# ESP32.net
KiCad netlist of a schematic drawn in Altium Designer
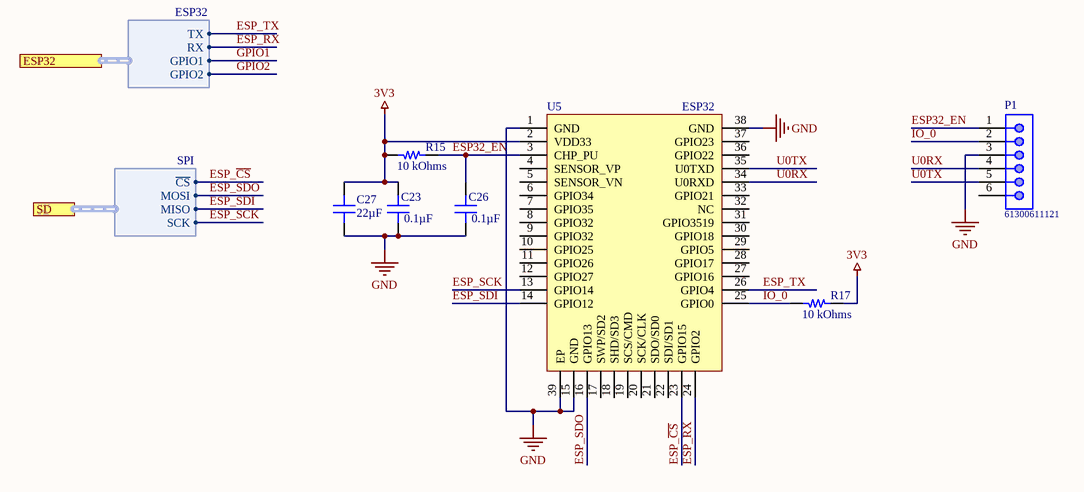
[diagram p0: ESP32.SchDoc]

(export (version "E")
  (design (tool "Eeschema 10.0.6"))
  (components
    (comp (ref "C23")
      (value "0.1µF")
      (footprint "CAP 0603_1608")
      (description "CAP CER 0.1UF 100V 0603 EPOXY")
      (fields
        (field (name "PART NUMBER") "GCG188R92A104KA03D")
        (field (name "MANUFACTURER") "Murata Electronics")
      )
      (libsource (lib "Celestial Altium Library - altium_library") (part "Capacitor"))
    )
    (comp (ref "C26")
      (value "0.1µF")
      (footprint "CAP 0603_1608")
      (description "CAP CER 0.1UF 100V 0603 EPOXY")
      (fields
        (field (name "PART NUMBER") "GCG188R92A104KA03D")
        (field (name "MANUFACTURER") "Murata Electronics")
      )
      (libsource (lib "Celestial Altium Library - altium_library") (part "Capacitor"))
    )
    (comp (ref "C27")
      (value "22µF")
      (footprint "CAP 0805_2012")
      (description "CAP CER 22UF 16V X5R 0805")
      (fields
        (field (name "PART NUMBER") "CL21A226MOQNNNE")
        (field (name "MANUFACTURER") "Samsung Electro-Mechanics")
      )
      (libsource (lib "Celestial Altium Library - altium_library") (part "Capacitor"))
    )
    (comp (ref "P1")
      (value "61300611121")
      (footprint "61300611121")
      (description "WR-PHD Pin Header, THT, pitch 2.54mm, Single Row, Vertical, 6p")
      (fields (field (name "MANUFACTURER") "Wurth Elektronik"))
      (libsource (lib "Altium_WR-PHD") (part "61300611121"))
    )
    (comp (ref "R15")
      (value "10 kOhms")
      (footprint "RES 0603_1608")
      (description "RES 10K OHM 0.1% 1/16W 0603")
      (fields
        (field (name "PART NUMBER") "RNCS0603BKE10K0")
        (field (name "MANUFACTURER") "Stackpole Electronics Inc")
      )
      (libsource (lib "Celestial Altium Library - altium_library") (part "Resistor"))
    )
    (comp (ref "R17")
      (value "10 kOhms")
      (footprint "RES 0603_1608")
      (description "RES 10K OHM 0.1% 1/16W 0603")
      (fields
        (field (name "PART NUMBER") "RNCS0603BKE10K0")
        (field (name "MANUFACTURER") "Stackpole Electronics Inc")
      )
      (libsource (lib "Celestial Altium Library - altium_library") (part "Resistor"))
    )
    (comp (ref "U5")
      (value "ESP32")
      (footprint "Espressif ESP32-WROOM-32")
      (libsource (lib "IC") (part "ESP32"))
    )
  )
  (nets
    (net (code "3") (name "/ESP32_EN") (class "Default")
      (node (ref "C26") (pin "1") (pinfunction "1_1") (pintype "passive"))
      (node (ref "P1") (pin "1") (pinfunction "1_1") (pintype "passive"))
      (node (ref "R15") (pin "1") (pinfunction "1_1") (pintype "passive"))
      (node (ref "U5") (pin "3") (pinfunction "CHP_PU_3") (pintype "passive"))
    )
    (net (code "4") (name "/ESP_RX") (class "Default")
      (node (ref "U5") (pin "24") (pinfunction "GPIO2_24") (pintype "passive"))
    )
    (net (code "5") (name "/ESP_SCK") (class "Default")
      (node (ref "U5") (pin "13") (pinfunction "GPIO14_13") (pintype "passive"))
    )
    (net (code "6") (name "/ESP_SDI") (class "Default")
      (node (ref "U5") (pin "14") (pinfunction "GPIO12_14") (pintype "passive"))
    )
    (net (code "7") (name "/ESP_SDO") (class "Default")
      (node (ref "U5") (pin "16") (pinfunction "GPIO13_16") (pintype "passive"))
    )
    (net (code "8") (name "/ESP_TX") (class "Default")
      (node (ref "U5") (pin "26") (pinfunction "GPIO4_26") (pintype "passive"))
    )
    (net (code "9") (name "/ESP_~{CS}") (class "Default")
      (node (ref "U5") (pin "23") (pinfunction "GPIO15_23") (pintype "passive"))
    )
    (net (code "12") (name "/IO_0") (class "Default")
      (node (ref "P1") (pin "2") (pinfunction "2_2") (pintype "passive"))
      (node (ref "R17") (pin "2") (pinfunction "2_2") (pintype "passive"))
      (node (ref "U5") (pin "25") (pinfunction "GPIO0_25") (pintype "passive"))
    )
    (net (code "13") (name "/U0RX") (class "Default")
      (node (ref "P1") (pin "4") (pinfunction "4_4") (pintype "passive"))
      (node (ref "U5") (pin "34") (pinfunction "U0RXD_34") (pintype "passive"))
    )
    (net (code "14") (name "/U0TX") (class "Default")
      (node (ref "P1") (pin "5") (pinfunction "5_5") (pintype "passive"))
      (node (ref "U5") (pin "35") (pinfunction "U0TXD_35") (pintype "passive"))
    )
    (net (code "17") (name "3V3") (class "Default")
      (node (ref "C23") (pin "1") (pinfunction "1_1") (pintype "passive"))
      (node (ref "C27") (pin "2") (pinfunction "2_2") (pintype "passive"))
      (node (ref "R15") (pin "2") (pinfunction "2_2") (pintype "passive"))
      (node (ref "R17") (pin "1") (pinfunction "1_1") (pintype "passive"))
      (node (ref "U5") (pin "2") (pinfunction "VDD33_2") (pintype "passive"))
    )
    (net (code "18") (name "GND") (class "Default")
      (node (ref "C23") (pin "2") (pinfunction "2_2") (pintype "passive"))
      (node (ref "C26") (pin "2") (pinfunction "2_2") (pintype "passive"))
      (node (ref "C27") (pin "1") (pinfunction "1_1") (pintype "passive"))
      (node (ref "P1") (pin "3") (pinfunction "3_3") (pintype "passive"))
      (node (ref "U5") (pin "1") (pinfunction "GND_1") (pintype "passive"))
      (node (ref "U5") (pin "15") (pinfunction "GND_15") (pintype "passive"))
      (node (ref "U5") (pin "38") (pinfunction "GND_38") (pintype "passive"))
      (node (ref "U5") (pin "39") (pinfunction "EP_39") (pintype "passive"))
    )
    (net (code "19") (name "unconnected-(P1-Pad6)") (class "Default")
      (node (ref "P1") (pin "6") (pinfunction "6_6") (pintype "passive"))
    )
    (net (code "20") (name "unconnected-(U5-GPIO5-Pad29)") (class "Default")
      (node (ref "U5") (pin "29") (pinfunction "GPIO5_29") (pintype "passive"))
    )
    (net (code "21") (name "unconnected-(U5-GPIO16-Pad27)") (class "Default")
      (node (ref "U5") (pin "27") (pinfunction "GPIO16_27") (pintype "passive"))
    )
    (net (code "22") (name "unconnected-(U5-GPIO17-Pad28)") (class "Default")
      (node (ref "U5") (pin "28") (pinfunction "GPIO17_28") (pintype "passive"))
    )
    (net (code "23") (name "unconnected-(U5-GPIO18-Pad30)") (class "Default")
      (node (ref "U5") (pin "30") (pinfunction "GPIO18_30") (pintype "passive"))
    )
    (net (code "24") (name "unconnected-(U5-GPIO21-Pad33)") (class "Default")
      (node (ref "U5") (pin "33") (pinfunction "GPIO21_33") (pintype "passive"))
    )
    (net (code "25") (name "unconnected-(U5-GPIO22-Pad36)") (class "Default")
      (node (ref "U5") (pin "36") (pinfunction "GPIO22_36") (pintype "passive"))
    )
    (net (code "26") (name "unconnected-(U5-GPIO23-Pad37)") (class "Default")
      (node (ref "U5") (pin "37") (pinfunction "GPIO23_37") (pintype "passive"))
    )
    (net (code "27") (name "unconnected-(U5-GPIO25-Pad10)") (class "Default")
      (node (ref "U5") (pin "10") (pinfunction "GPIO25_10") (pintype "passive"))
    )
    (net (code "28") (name "unconnected-(U5-GPIO26-Pad11)") (class "Default")
      (node (ref "U5") (pin "11") (pinfunction "GPIO26_11") (pintype "passive"))
    )
    (net (code "29") (name "unconnected-(U5-GPIO27-Pad12)") (class "Default")
      (node (ref "U5") (pin "12") (pinfunction "GPIO27_12") (pintype "passive"))
    )
    (net (code "30") (name "unconnected-(U5-GPIO32-Pad8)") (class "Default")
      (node (ref "U5") (pin "8") (pinfunction "GPIO32_8") (pintype "passive"))
    )
    (net (code "31") (name "unconnected-(U5-GPIO32-Pad9)") (class "Default")
      (node (ref "U5") (pin "9") (pinfunction "GPIO32_9") (pintype "passive"))
    )
    (net (code "32") (name "unconnected-(U5-GPIO34-Pad6)") (class "Default")
      (node (ref "U5") (pin "6") (pinfunction "GPIO34_6") (pintype "passive"))
    )
    (net (code "33") (name "unconnected-(U5-GPIO35-Pad7)") (class "Default")
      (node (ref "U5") (pin "7") (pinfunction "GPIO35_7") (pintype "passive"))
    )
    (net (code "34") (name "unconnected-(U5-GPIO3519-Pad31)") (class "Default")
      (node (ref "U5") (pin "31") (pinfunction "GPIO3519_31") (pintype "passive"))
    )
    (net (code "35") (name "unconnected-(U5-NC-Pad32)") (class "Default")
      (node (ref "U5") (pin "32") (pinfunction "NC_32") (pintype "passive"))
    )
    (net (code "36") (name "unconnected-(U5-SCK{slash}CLK-Pad20)") (class "Default")
      (node (ref "U5") (pin "20") (pinfunction "SCK/CLK_20") (pintype "passive"))
    )
    (net (code "37") (name "unconnected-(U5-SCS{slash}CMD-Pad19)") (class "Default")
      (node (ref "U5") (pin "19") (pinfunction "SCS/CMD_19") (pintype "passive"))
    )
    (net (code "38") (name "unconnected-(U5-SDI{slash}SD1-Pad22)") (class "Default")
      (node (ref "U5") (pin "22") (pinfunction "SDI/SD1_22") (pintype "passive"))
    )
    (net (code "39") (name "unconnected-(U5-SDO{slash}SD0-Pad21)") (class "Default")
      (node (ref "U5") (pin "21") (pinfunction "SDO/SD0_21") (pintype "passive"))
    )
    (net (code "40") (name "unconnected-(U5-SENSOR_VN-Pad5)") (class "Default")
      (node (ref "U5") (pin "5") (pinfunction "SENSOR_VN_5") (pintype "passive"))
    )
    (net (code "41") (name "unconnected-(U5-SENSOR_VP-Pad4)") (class "Default")
      (node (ref "U5") (pin "4") (pinfunction "SENSOR_VP_4") (pintype "passive"))
    )
    (net (code "42") (name "unconnected-(U5-SHD{slash}SD3-Pad18)") (class "Default")
      (node (ref "U5") (pin "18") (pinfunction "SHD/SD3_18") (pintype "passive"))
    )
    (net (code "43") (name "unconnected-(U5-SWP{slash}SD2-Pad17)") (class "Default")
      (node (ref "U5") (pin "17") (pinfunction "SWP/SD2_17") (pintype "passive"))
    )
  )
)
